# rpi-adapter_V0.net
KiCad netlist of a schematic drawn in EAGLE
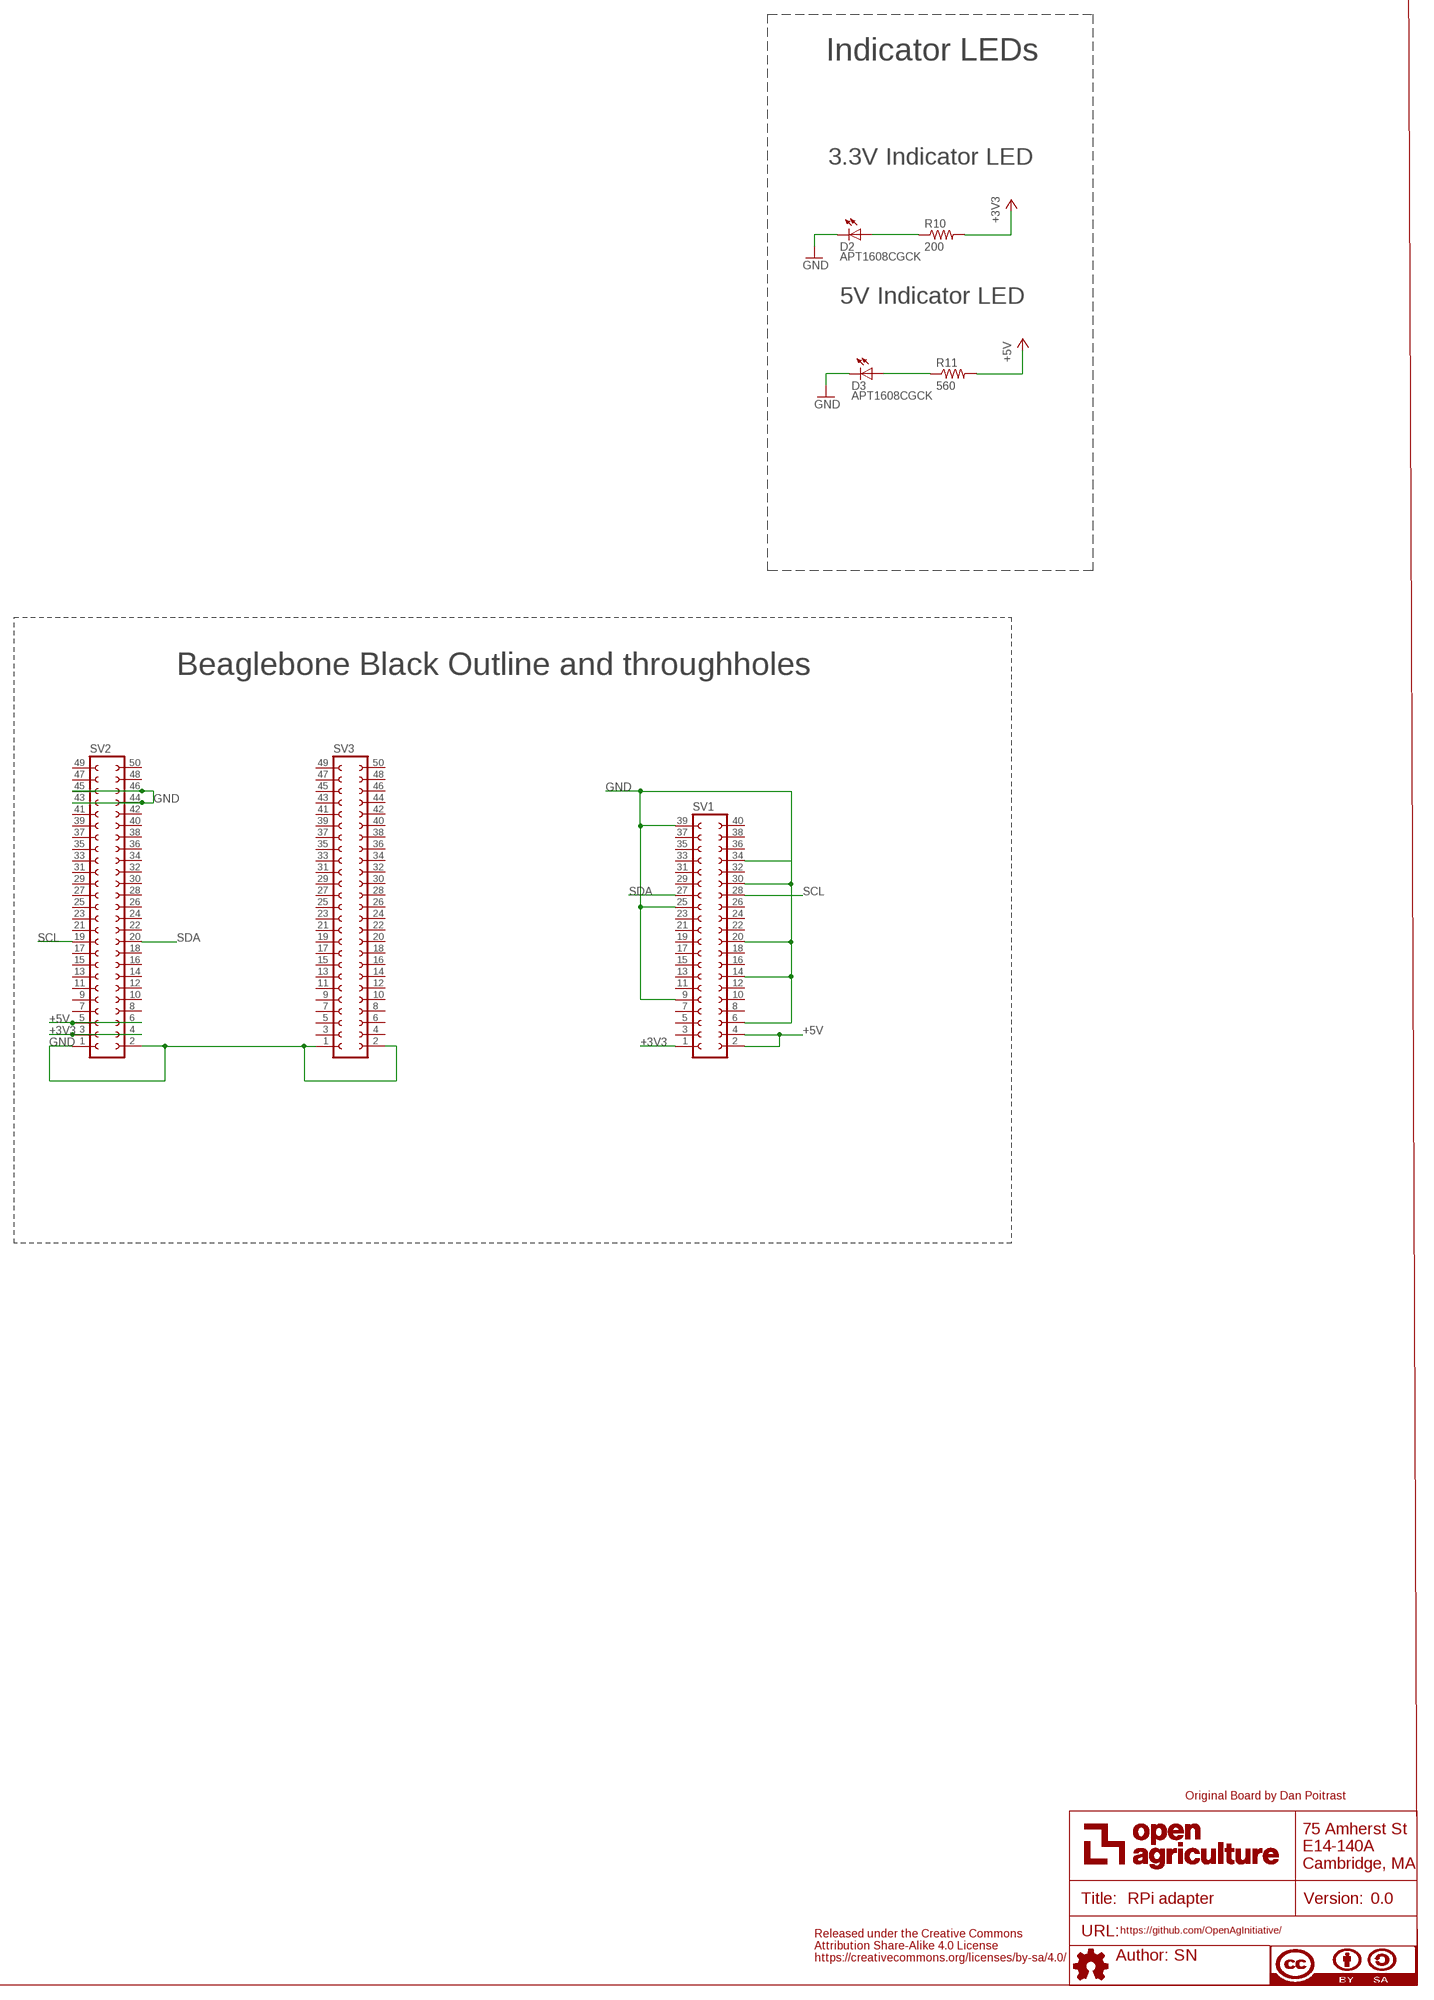
[diagram p0: schematic, sheet 1]

(export (version "E")
  (design (tool "Eeschema 10.0.6"))
  (components
    (comp (ref "ATTRIBUTES")
      (value "DOCFIELD")
      (footprint "eagle-import:DOCFIELD")
      (description "RPi to BBB adapter")
      (fields
        (field (name "TITLE") "Example Template")
        (field (name "AUTHOR") "XX")
        (field (name "VER") "1.0")
        (field (name "URL") "https://github.com/OpenAgInitiative/openag_eagle_template")
        (field (name "AUTHOR_1") "SN")
        (field (name "TITLE_1") "RPi adapter")
        (field (name "URL_1") "https://github.com/OpenAgInitiative/")
        (field (name "VER_1") "0.0")
      )
      (libsource (lib "eagle-import") (part "DOCFIELD"))
    )
    (comp (ref "D2")
      (value "APT1608CGCK")
      (footprint "eagle-import:CHIPLED_0603")
      (libsource (lib "eagle-import") (part "APT1608CGCK"))
    )
    (comp (ref "D3")
      (value "APT1608CGCK")
      (footprint "eagle-import:CHIPLED_0603")
      (libsource (lib "eagle-import") (part "APT1608CGCK"))
    )
    (comp (ref "R10")
      (value "200")
      (footprint "eagle-import:RC0603N")
      (libsource (lib "eagle-import") (part "100OHM-RC0603JR-07100RL"))
    )
    (comp (ref "R11")
      (value "560")
      (footprint "eagle-import:RC0603N")
      (libsource (lib "eagle-import") (part "100OHM-RC0603JR-07100RL"))
    )
    (comp (ref "SV1")
      (value "FE20-2")
      (footprint "eagle-import:FE20-2")
      (libsource (lib "eagle-import") (part "FE20-2"))
    )
    (comp (ref "SV2")
      (value "FE25-2")
      (footprint "eagle-import:FE25-2")
      (libsource (lib "eagle-import") (part "FE25-2"))
    )
    (comp (ref "SV3")
      (value "FE25-2")
      (footprint "eagle-import:FE25-2")
      (libsource (lib "eagle-import") (part "FE25-2"))
    )
  )
  (nets
    (net (code "1") (name "+3V3") (class "Default")
      (node (ref "R10") (pin "2") (pinfunction "2_2") (pintype "passive"))
      (node (ref "SV1") (pin "1") (pinfunction "1_1") (pintype "passive"))
      (node (ref "SV2") (pin "3") (pinfunction "3_3") (pintype "passive"))
      (node (ref "SV2") (pin "4") (pinfunction "4_4") (pintype "passive"))
    )
    (net (code "2") (name "+5V") (class "Default")
      (node (ref "R11") (pin "2") (pinfunction "2_2") (pintype "passive"))
      (node (ref "SV1") (pin "2") (pinfunction "2_2") (pintype "passive"))
      (node (ref "SV1") (pin "4") (pinfunction "4_4") (pintype "passive"))
      (node (ref "SV2") (pin "5") (pinfunction "5_5") (pintype "passive"))
      (node (ref "SV2") (pin "6") (pinfunction "6_6") (pintype "passive"))
    )
    (net (code "3") (name "/SCL") (class "Default")
      (node (ref "SV1") (pin "28") (pinfunction "28_28") (pintype "passive"))
      (node (ref "SV2") (pin "19") (pinfunction "19_19") (pintype "passive"))
    )
    (net (code "4") (name "/SDA") (class "Default")
      (node (ref "SV1") (pin "27") (pinfunction "27_27") (pintype "passive"))
      (node (ref "SV2") (pin "20") (pinfunction "20_20") (pintype "passive"))
    )
    (net (code "5") (name "GND") (class "Default")
      (node (ref "D2") (pin "C") (pinfunction "C_C") (pintype "passive"))
      (node (ref "D3") (pin "C") (pinfunction "C_C") (pintype "passive"))
      (node (ref "SV1") (pin "14") (pinfunction "14_14") (pintype "passive"))
      (node (ref "SV1") (pin "20") (pinfunction "20_20") (pintype "passive"))
      (node (ref "SV1") (pin "25") (pinfunction "25_25") (pintype "passive"))
      (node (ref "SV1") (pin "30") (pinfunction "30_30") (pintype "passive"))
      (node (ref "SV1") (pin "34") (pinfunction "34_34") (pintype "passive"))
      (node (ref "SV1") (pin "39") (pinfunction "39_39") (pintype "passive"))
      (node (ref "SV1") (pin "6") (pinfunction "6_6") (pintype "passive"))
      (node (ref "SV1") (pin "9") (pinfunction "9_9") (pintype "passive"))
      (node (ref "SV2") (pin "1") (pinfunction "1_1") (pintype "passive"))
      (node (ref "SV2") (pin "2") (pinfunction "2_2") (pintype "passive"))
      (node (ref "SV2") (pin "43") (pinfunction "43_43") (pintype "passive"))
      (node (ref "SV2") (pin "44") (pinfunction "44_44") (pintype "passive"))
      (node (ref "SV2") (pin "45") (pinfunction "45_45") (pintype "passive"))
      (node (ref "SV2") (pin "46") (pinfunction "46_46") (pintype "passive"))
      (node (ref "SV3") (pin "1") (pinfunction "1_1") (pintype "passive"))
      (node (ref "SV3") (pin "2") (pinfunction "2_2") (pintype "passive"))
    )
    (net (code "6") (name "Net-(D2-PadA)") (class "Default")
      (node (ref "D2") (pin "A") (pinfunction "A_A") (pintype "passive"))
      (node (ref "R10") (pin "1") (pinfunction "1_1") (pintype "passive"))
    )
    (net (code "7") (name "Net-(D3-PadA)") (class "Default")
      (node (ref "D3") (pin "A") (pinfunction "A_A") (pintype "passive"))
      (node (ref "R11") (pin "1") (pinfunction "1_1") (pintype "passive"))
    )
    (net (code "8") (name "unconnected-(SV1-Pad3)") (class "Default")
      (node (ref "SV1") (pin "3") (pinfunction "3_3") (pintype "passive"))
    )
    (net (code "9") (name "unconnected-(SV1-Pad5)") (class "Default")
      (node (ref "SV1") (pin "5") (pinfunction "5_5") (pintype "passive"))
    )
    (net (code "10") (name "unconnected-(SV1-Pad7)") (class "Default")
      (node (ref "SV1") (pin "7") (pinfunction "7_7") (pintype "passive"))
    )
    (net (code "11") (name "unconnected-(SV1-Pad8)") (class "Default")
      (node (ref "SV1") (pin "8") (pinfunction "8_8") (pintype "passive"))
    )
    (net (code "12") (name "unconnected-(SV1-Pad10)") (class "Default")
      (node (ref "SV1") (pin "10") (pinfunction "10_10") (pintype "passive"))
    )
    (net (code "13") (name "unconnected-(SV1-Pad11)") (class "Default")
      (node (ref "SV1") (pin "11") (pinfunction "11_11") (pintype "passive"))
    )
    (net (code "14") (name "unconnected-(SV1-Pad12)") (class "Default")
      (node (ref "SV1") (pin "12") (pinfunction "12_12") (pintype "passive"))
    )
    (net (code "15") (name "unconnected-(SV1-Pad13)") (class "Default")
      (node (ref "SV1") (pin "13") (pinfunction "13_13") (pintype "passive"))
    )
    (net (code "16") (name "unconnected-(SV1-Pad15)") (class "Default")
      (node (ref "SV1") (pin "15") (pinfunction "15_15") (pintype "passive"))
    )
    (net (code "17") (name "unconnected-(SV1-Pad16)") (class "Default")
      (node (ref "SV1") (pin "16") (pinfunction "16_16") (pintype "passive"))
    )
    (net (code "18") (name "unconnected-(SV1-Pad17)") (class "Default")
      (node (ref "SV1") (pin "17") (pinfunction "17_17") (pintype "passive"))
    )
    (net (code "19") (name "unconnected-(SV1-Pad18)") (class "Default")
      (node (ref "SV1") (pin "18") (pinfunction "18_18") (pintype "passive"))
    )
    (net (code "20") (name "unconnected-(SV1-Pad19)") (class "Default")
      (node (ref "SV1") (pin "19") (pinfunction "19_19") (pintype "passive"))
    )
    (net (code "21") (name "unconnected-(SV1-Pad21)") (class "Default")
      (node (ref "SV1") (pin "21") (pinfunction "21_21") (pintype "passive"))
    )
    (net (code "22") (name "unconnected-(SV1-Pad22)") (class "Default")
      (node (ref "SV1") (pin "22") (pinfunction "22_22") (pintype "passive"))
    )
    (net (code "23") (name "unconnected-(SV1-Pad23)") (class "Default")
      (node (ref "SV1") (pin "23") (pinfunction "23_23") (pintype "passive"))
    )
    (net (code "24") (name "unconnected-(SV1-Pad24)") (class "Default")
      (node (ref "SV1") (pin "24") (pinfunction "24_24") (pintype "passive"))
    )
    (net (code "25") (name "unconnected-(SV1-Pad26)") (class "Default")
      (node (ref "SV1") (pin "26") (pinfunction "26_26") (pintype "passive"))
    )
    (net (code "26") (name "unconnected-(SV1-Pad29)") (class "Default")
      (node (ref "SV1") (pin "29") (pinfunction "29_29") (pintype "passive"))
    )
    (net (code "27") (name "unconnected-(SV1-Pad31)") (class "Default")
      (node (ref "SV1") (pin "31") (pinfunction "31_31") (pintype "passive"))
    )
    (net (code "28") (name "unconnected-(SV1-Pad32)") (class "Default")
      (node (ref "SV1") (pin "32") (pinfunction "32_32") (pintype "passive"))
    )
    (net (code "29") (name "unconnected-(SV1-Pad33)") (class "Default")
      (node (ref "SV1") (pin "33") (pinfunction "33_33") (pintype "passive"))
    )
    (net (code "30") (name "unconnected-(SV1-Pad35)") (class "Default")
      (node (ref "SV1") (pin "35") (pinfunction "35_35") (pintype "passive"))
    )
    (net (code "31") (name "unconnected-(SV1-Pad36)") (class "Default")
      (node (ref "SV1") (pin "36") (pinfunction "36_36") (pintype "passive"))
    )
    (net (code "32") (name "unconnected-(SV1-Pad37)") (class "Default")
      (node (ref "SV1") (pin "37") (pinfunction "37_37") (pintype "passive"))
    )
    (net (code "33") (name "unconnected-(SV1-Pad38)") (class "Default")
      (node (ref "SV1") (pin "38") (pinfunction "38_38") (pintype "passive"))
    )
    (net (code "34") (name "unconnected-(SV1-Pad40)") (class "Default")
      (node (ref "SV1") (pin "40") (pinfunction "40_40") (pintype "passive"))
    )
    (net (code "35") (name "unconnected-(SV2-Pad7)") (class "Default")
      (node (ref "SV2") (pin "7") (pinfunction "7_7") (pintype "passive"))
    )
    (net (code "36") (name "unconnected-(SV2-Pad8)") (class "Default")
      (node (ref "SV2") (pin "8") (pinfunction "8_8") (pintype "passive"))
    )
    (net (code "37") (name "unconnected-(SV2-Pad9)") (class "Default")
      (node (ref "SV2") (pin "9") (pinfunction "9_9") (pintype "passive"))
    )
    (net (code "38") (name "unconnected-(SV2-Pad10)") (class "Default")
      (node (ref "SV2") (pin "10") (pinfunction "10_10") (pintype "passive"))
    )
    (net (code "39") (name "unconnected-(SV2-Pad11)") (class "Default")
      (node (ref "SV2") (pin "11") (pinfunction "11_11") (pintype "passive"))
    )
    (net (code "40") (name "unconnected-(SV2-Pad12)") (class "Default")
      (node (ref "SV2") (pin "12") (pinfunction "12_12") (pintype "passive"))
    )
    (net (code "41") (name "unconnected-(SV2-Pad13)") (class "Default")
      (node (ref "SV2") (pin "13") (pinfunction "13_13") (pintype "passive"))
    )
    (net (code "42") (name "unconnected-(SV2-Pad14)") (class "Default")
      (node (ref "SV2") (pin "14") (pinfunction "14_14") (pintype "passive"))
    )
    (net (code "43") (name "unconnected-(SV2-Pad15)") (class "Default")
      (node (ref "SV2") (pin "15") (pinfunction "15_15") (pintype "passive"))
    )
    (net (code "44") (name "unconnected-(SV2-Pad16)") (class "Default")
      (node (ref "SV2") (pin "16") (pinfunction "16_16") (pintype "passive"))
    )
    (net (code "45") (name "unconnected-(SV2-Pad17)") (class "Default")
      (node (ref "SV2") (pin "17") (pinfunction "17_17") (pintype "passive"))
    )
    (net (code "46") (name "unconnected-(SV2-Pad18)") (class "Default")
      (node (ref "SV2") (pin "18") (pinfunction "18_18") (pintype "passive"))
    )
    (net (code "47") (name "unconnected-(SV2-Pad21)") (class "Default")
      (node (ref "SV2") (pin "21") (pinfunction "21_21") (pintype "passive"))
    )
    (net (code "48") (name "unconnected-(SV2-Pad22)") (class "Default")
      (node (ref "SV2") (pin "22") (pinfunction "22_22") (pintype "passive"))
    )
    (net (code "49") (name "unconnected-(SV2-Pad23)") (class "Default")
      (node (ref "SV2") (pin "23") (pinfunction "23_23") (pintype "passive"))
    )
    (net (code "50") (name "unconnected-(SV2-Pad24)") (class "Default")
      (node (ref "SV2") (pin "24") (pinfunction "24_24") (pintype "passive"))
    )
    (net (code "51") (name "unconnected-(SV2-Pad25)") (class "Default")
      (node (ref "SV2") (pin "25") (pinfunction "25_25") (pintype "passive"))
    )
    (net (code "52") (name "unconnected-(SV2-Pad26)") (class "Default")
      (node (ref "SV2") (pin "26") (pinfunction "26_26") (pintype "passive"))
    )
    (net (code "53") (name "unconnected-(SV2-Pad27)") (class "Default")
      (node (ref "SV2") (pin "27") (pinfunction "27_27") (pintype "passive"))
    )
    (net (code "54") (name "unconnected-(SV2-Pad28)") (class "Default")
      (node (ref "SV2") (pin "28") (pinfunction "28_28") (pintype "passive"))
    )
    (net (code "55") (name "unconnected-(SV2-Pad29)") (class "Default")
      (node (ref "SV2") (pin "29") (pinfunction "29_29") (pintype "passive"))
    )
    (net (code "56") (name "unconnected-(SV2-Pad30)") (class "Default")
      (node (ref "SV2") (pin "30") (pinfunction "30_30") (pintype "passive"))
    )
    (net (code "57") (name "unconnected-(SV2-Pad31)") (class "Default")
      (node (ref "SV2") (pin "31") (pinfunction "31_31") (pintype "passive"))
    )
    (net (code "58") (name "unconnected-(SV2-Pad32)") (class "Default")
      (node (ref "SV2") (pin "32") (pinfunction "32_32") (pintype "passive"))
    )
    (net (code "59") (name "unconnected-(SV2-Pad33)") (class "Default")
      (node (ref "SV2") (pin "33") (pinfunction "33_33") (pintype "passive"))
    )
    (net (code "60") (name "unconnected-(SV2-Pad34)") (class "Default")
      (node (ref "SV2") (pin "34") (pinfunction "34_34") (pintype "passive"))
    )
    (net (code "61") (name "unconnected-(SV2-Pad35)") (class "Default")
      (node (ref "SV2") (pin "35") (pinfunction "35_35") (pintype "passive"))
    )
    (net (code "62") (name "unconnected-(SV2-Pad36)") (class "Default")
      (node (ref "SV2") (pin "36") (pinfunction "36_36") (pintype "passive"))
    )
    (net (code "63") (name "unconnected-(SV2-Pad37)") (class "Default")
      (node (ref "SV2") (pin "37") (pinfunction "37_37") (pintype "passive"))
    )
    (net (code "64") (name "unconnected-(SV2-Pad38)") (class "Default")
      (node (ref "SV2") (pin "38") (pinfunction "38_38") (pintype "passive"))
    )
    (net (code "65") (name "unconnected-(SV2-Pad39)") (class "Default")
      (node (ref "SV2") (pin "39") (pinfunction "39_39") (pintype "passive"))
    )
    (net (code "66") (name "unconnected-(SV2-Pad40)") (class "Default")
      (node (ref "SV2") (pin "40") (pinfunction "40_40") (pintype "passive"))
    )
    (net (code "67") (name "unconnected-(SV2-Pad41)") (class "Default")
      (node (ref "SV2") (pin "41") (pinfunction "41_41") (pintype "passive"))
    )
    (net (code "68") (name "unconnected-(SV2-Pad42)") (class "Default")
      (node (ref "SV2") (pin "42") (pinfunction "42_42") (pintype "passive"))
    )
    (net (code "69") (name "unconnected-(SV2-Pad47)") (class "Default")
      (node (ref "SV2") (pin "47") (pinfunction "47_47") (pintype "passive"))
    )
    (net (code "70") (name "unconnected-(SV2-Pad48)") (class "Default")
      (node (ref "SV2") (pin "48") (pinfunction "48_48") (pintype "passive"))
    )
    (net (code "71") (name "unconnected-(SV2-Pad49)") (class "Default")
      (node (ref "SV2") (pin "49") (pinfunction "49_49") (pintype "passive"))
    )
    (net (code "72") (name "unconnected-(SV2-Pad50)") (class "Default")
      (node (ref "SV2") (pin "50") (pinfunction "50_50") (pintype "passive"))
    )
    (net (code "73") (name "unconnected-(SV3-Pad3)") (class "Default")
      (node (ref "SV3") (pin "3") (pinfunction "3_3") (pintype "passive"))
    )
    (net (code "74") (name "unconnected-(SV3-Pad4)") (class "Default")
      (node (ref "SV3") (pin "4") (pinfunction "4_4") (pintype "passive"))
    )
    (net (code "75") (name "unconnected-(SV3-Pad5)") (class "Default")
      (node (ref "SV3") (pin "5") (pinfunction "5_5") (pintype "passive"))
    )
    (net (code "76") (name "unconnected-(SV3-Pad6)") (class "Default")
      (node (ref "SV3") (pin "6") (pinfunction "6_6") (pintype "passive"))
    )
    (net (code "77") (name "unconnected-(SV3-Pad7)") (class "Default")
      (node (ref "SV3") (pin "7") (pinfunction "7_7") (pintype "passive"))
    )
    (net (code "78") (name "unconnected-(SV3-Pad8)") (class "Default")
      (node (ref "SV3") (pin "8") (pinfunction "8_8") (pintype "passive"))
    )
    (net (code "79") (name "unconnected-(SV3-Pad9)") (class "Default")
      (node (ref "SV3") (pin "9") (pinfunction "9_9") (pintype "passive"))
    )
    (net (code "80") (name "unconnected-(SV3-Pad10)") (class "Default")
      (node (ref "SV3") (pin "10") (pinfunction "10_10") (pintype "passive"))
    )
    (net (code "81") (name "unconnected-(SV3-Pad11)") (class "Default")
      (node (ref "SV3") (pin "11") (pinfunction "11_11") (pintype "passive"))
    )
    (net (code "82") (name "unconnected-(SV3-Pad12)") (class "Default")
      (node (ref "SV3") (pin "12") (pinfunction "12_12") (pintype "passive"))
    )
    (net (code "83") (name "unconnected-(SV3-Pad13)") (class "Default")
      (node (ref "SV3") (pin "13") (pinfunction "13_13") (pintype "passive"))
    )
    (net (code "84") (name "unconnected-(SV3-Pad14)") (class "Default")
      (node (ref "SV3") (pin "14") (pinfunction "14_14") (pintype "passive"))
    )
    (net (code "85") (name "unconnected-(SV3-Pad15)") (class "Default")
      (node (ref "SV3") (pin "15") (pinfunction "15_15") (pintype "passive"))
    )
    (net (code "86") (name "unconnected-(SV3-Pad16)") (class "Default")
      (node (ref "SV3") (pin "16") (pinfunction "16_16") (pintype "passive"))
    )
    (net (code "87") (name "unconnected-(SV3-Pad17)") (class "Default")
      (node (ref "SV3") (pin "17") (pinfunction "17_17") (pintype "passive"))
    )
    (net (code "88") (name "unconnected-(SV3-Pad18)") (class "Default")
      (node (ref "SV3") (pin "18") (pinfunction "18_18") (pintype "passive"))
    )
    (net (code "89") (name "unconnected-(SV3-Pad19)") (class "Default")
      (node (ref "SV3") (pin "19") (pinfunction "19_19") (pintype "passive"))
    )
    (net (code "90") (name "unconnected-(SV3-Pad20)") (class "Default")
      (node (ref "SV3") (pin "20") (pinfunction "20_20") (pintype "passive"))
    )
    (net (code "91") (name "unconnected-(SV3-Pad21)") (class "Default")
      (node (ref "SV3") (pin "21") (pinfunction "21_21") (pintype "passive"))
    )
    (net (code "92") (name "unconnected-(SV3-Pad22)") (class "Default")
      (node (ref "SV3") (pin "22") (pinfunction "22_22") (pintype "passive"))
    )
    (net (code "93") (name "unconnected-(SV3-Pad23)") (class "Default")
      (node (ref "SV3") (pin "23") (pinfunction "23_23") (pintype "passive"))
    )
    (net (code "94") (name "unconnected-(SV3-Pad24)") (class "Default")
      (node (ref "SV3") (pin "24") (pinfunction "24_24") (pintype "passive"))
    )
    (net (code "95") (name "unconnected-(SV3-Pad25)") (class "Default")
      (node (ref "SV3") (pin "25") (pinfunction "25_25") (pintype "passive"))
    )
    (net (code "96") (name "unconnected-(SV3-Pad26)") (class "Default")
      (node (ref "SV3") (pin "26") (pinfunction "26_26") (pintype "passive"))
    )
    (net (code "97") (name "unconnected-(SV3-Pad27)") (class "Default")
      (node (ref "SV3") (pin "27") (pinfunction "27_27") (pintype "passive"))
    )
    (net (code "98") (name "unconnected-(SV3-Pad28)") (class "Default")
      (node (ref "SV3") (pin "28") (pinfunction "28_28") (pintype "passive"))
    )
    (net (code "99") (name "unconnected-(SV3-Pad29)") (class "Default")
      (node (ref "SV3") (pin "29") (pinfunction "29_29") (pintype "passive"))
    )
    (net (code "100") (name "unconnected-(SV3-Pad30)") (class "Default")
      (node (ref "SV3") (pin "30") (pinfunction "30_30") (pintype "passive"))
    )
    (net (code "101") (name "unconnected-(SV3-Pad31)") (class "Default")
      (node (ref "SV3") (pin "31") (pinfunction "31_31") (pintype "passive"))
    )
    (net (code "102") (name "unconnected-(SV3-Pad32)") (class "Default")
      (node (ref "SV3") (pin "32") (pinfunction "32_32") (pintype "passive"))
    )
    (net (code "103") (name "unconnected-(SV3-Pad33)") (class "Default")
      (node (ref "SV3") (pin "33") (pinfunction "33_33") (pintype "passive"))
    )
    (net (code "104") (name "unconnected-(SV3-Pad34)") (class "Default")
      (node (ref "SV3") (pin "34") (pinfunction "34_34") (pintype "passive"))
    )
    (net (code "105") (name "unconnected-(SV3-Pad35)") (class "Default")
      (node (ref "SV3") (pin "35") (pinfunction "35_35") (pintype "passive"))
    )
    (net (code "106") (name "unconnected-(SV3-Pad36)") (class "Default")
      (node (ref "SV3") (pin "36") (pinfunction "36_36") (pintype "passive"))
    )
    (net (code "107") (name "unconnected-(SV3-Pad37)") (class "Default")
      (node (ref "SV3") (pin "37") (pinfunction "37_37") (pintype "passive"))
    )
    (net (code "108") (name "unconnected-(SV3-Pad38)") (class "Default")
      (node (ref "SV3") (pin "38") (pinfunction "38_38") (pintype "passive"))
    )
    (net (code "109") (name "unconnected-(SV3-Pad39)") (class "Default")
      (node (ref "SV3") (pin "39") (pinfunction "39_39") (pintype "passive"))
    )
    (net (code "110") (name "unconnected-(SV3-Pad40)") (class "Default")
      (node (ref "SV3") (pin "40") (pinfunction "40_40") (pintype "passive"))
    )
    (net (code "111") (name "unconnected-(SV3-Pad41)") (class "Default")
      (node (ref "SV3") (pin "41") (pinfunction "41_41") (pintype "passive"))
    )
    (net (code "112") (name "unconnected-(SV3-Pad42)") (class "Default")
      (node (ref "SV3") (pin "42") (pinfunction "42_42") (pintype "passive"))
    )
    (net (code "113") (name "unconnected-(SV3-Pad43)") (class "Default")
      (node (ref "SV3") (pin "43") (pinfunction "43_43") (pintype "passive"))
    )
    (net (code "114") (name "unconnected-(SV3-Pad44)") (class "Default")
      (node (ref "SV3") (pin "44") (pinfunction "44_44") (pintype "passive"))
    )
    (net (code "115") (name "unconnected-(SV3-Pad45)") (class "Default")
      (node (ref "SV3") (pin "45") (pinfunction "45_45") (pintype "passive"))
    )
    (net (code "116") (name "unconnected-(SV3-Pad46)") (class "Default")
      (node (ref "SV3") (pin "46") (pinfunction "46_46") (pintype "passive"))
    )
    (net (code "117") (name "unconnected-(SV3-Pad47)") (class "Default")
      (node (ref "SV3") (pin "47") (pinfunction "47_47") (pintype "passive"))
    )
    (net (code "118") (name "unconnected-(SV3-Pad48)") (class "Default")
      (node (ref "SV3") (pin "48") (pinfunction "48_48") (pintype "passive"))
    )
    (net (code "119") (name "unconnected-(SV3-Pad49)") (class "Default")
      (node (ref "SV3") (pin "49") (pinfunction "49_49") (pintype "passive"))
    )
    (net (code "120") (name "unconnected-(SV3-Pad50)") (class "Default")
      (node (ref "SV3") (pin "50") (pinfunction "50_50") (pintype "passive"))
    )
  )
)
